# 02_AFE.net
KiCad netlist of a schematic drawn in Altium Designer
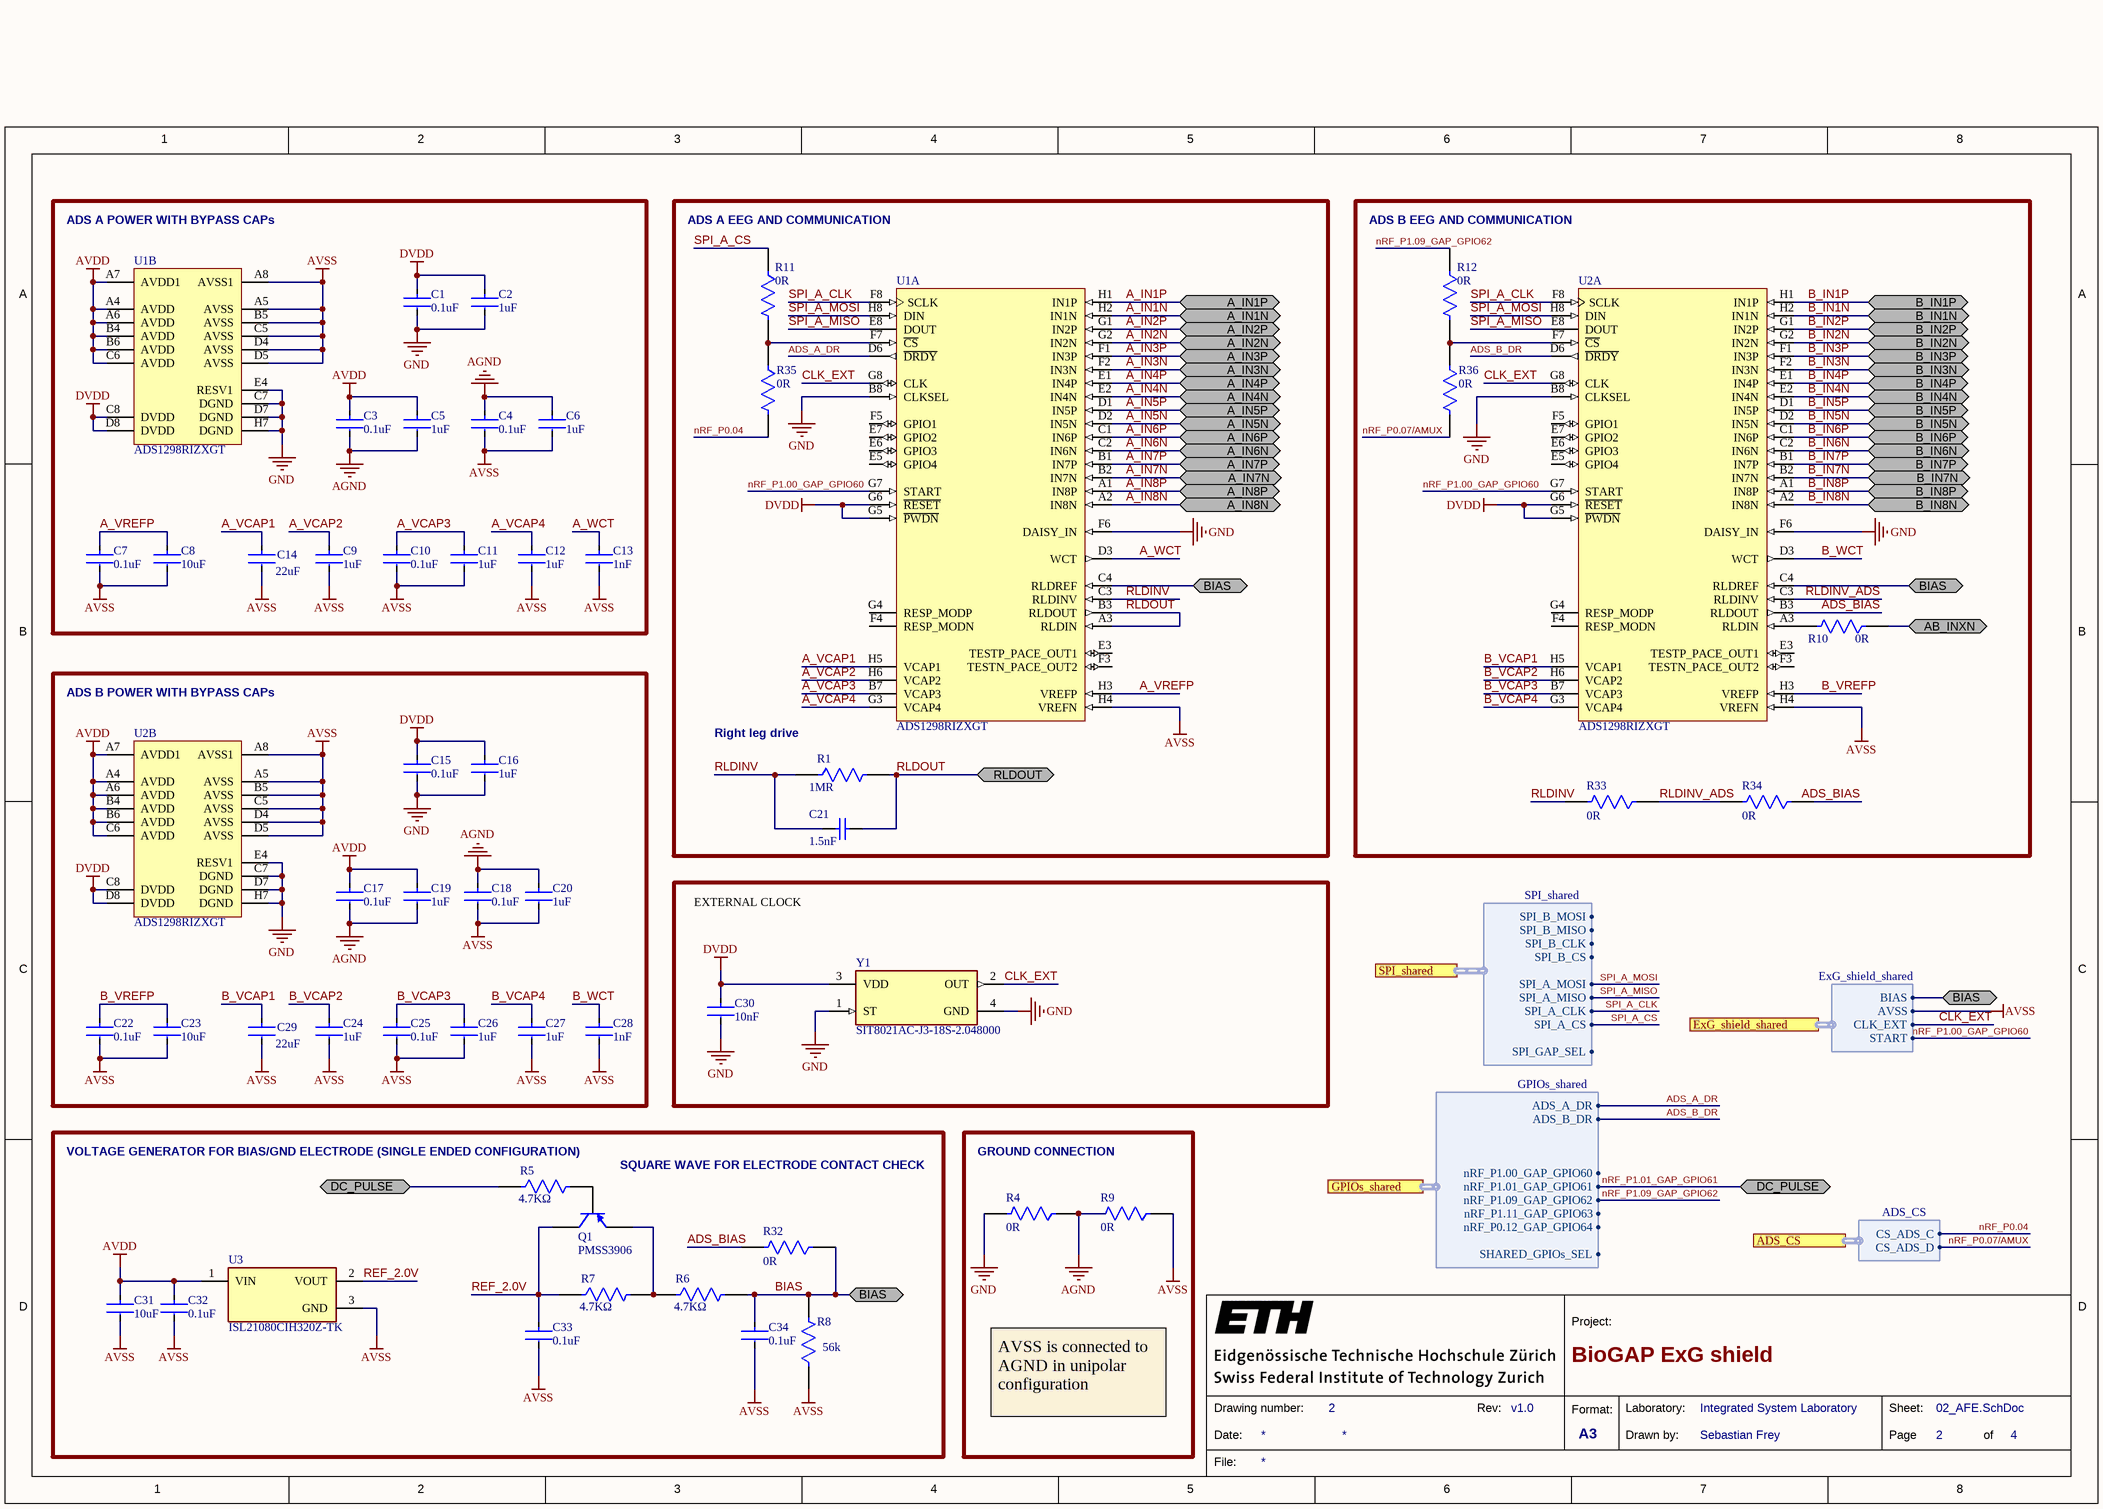
[diagram p0: 02_AFE.SchDoc]

(export (version "E")
  (design (tool "Eeschema 10.0.6"))
  (components
    (comp (ref "C1")
      (value "CL05A104KA5NNNC")
      (footprint "FP-CL278-IPC_C")
      (description "Cap Ceramic 100nF 25V X5R ±10% SMD 0402 +85°C Paper T/R")
      (fields
        (field (name "VOLTAGE") "25V")
        (field (name "TOLERANCE") "10%")
        (field (name "CAPACITANCE") "0.1uF")
      )
      (libsource (lib "Altium Content Vault") (part "b4654b650e69147ec39a6b967a45e02"))
    )
    (comp (ref "C2")
      (value "CL05A105KP5NNNC")
      (footprint "FP-CL511-IPC_C")
      (description "Cap Ceramic 1uF 10V X5R ±10% SMD 0402 +85°C Paper T/R")
      (fields (field (name "CAPACITANCE") "1uF") (field (name "TOLERANCE") "10%"))
      (libsource (lib "Altium Content Vault") (part "b4654b650e69147ec39a6b967a45e02"))
    )
    (comp (ref "C3")
      (value "CL05A104KA5NNNC")
      (footprint "FP-CL278-IPC_C")
      (description "Cap Ceramic 100nF 25V X5R ±10% SMD 0402 +85°C Paper T/R")
      (fields
        (field (name "VOLTAGE") "25V")
        (field (name "TOLERANCE") "10%")
        (field (name "CAPACITANCE") "0.1uF")
      )
      (libsource (lib "Altium Content Vault") (part "b4654b650e69147ec39a6b967a45e02"))
    )
    (comp (ref "C4")
      (value "CL05A104KA5NNNC")
      (footprint "FP-CL278-IPC_C")
      (description "Cap Ceramic 100nF 25V X5R ±10% SMD 0402 +85°C Paper T/R")
      (fields
        (field (name "VOLTAGE") "25V")
        (field (name "TOLERANCE") "10%")
        (field (name "CAPACITANCE") "0.1uF")
      )
      (libsource (lib "Altium Content Vault") (part "b4654b650e69147ec39a6b967a45e02"))
    )
    (comp (ref "C5")
      (value "CL05A105KP5NNNC")
      (footprint "FP-CL511-IPC_C")
      (description "Cap Ceramic 1uF 10V X5R ±10% SMD 0402 +85°C Paper T/R")
      (fields (field (name "CAPACITANCE") "1uF") (field (name "TOLERANCE") "10%"))
      (libsource (lib "Altium Content Vault") (part "b4654b650e69147ec39a6b967a45e02"))
    )
    (comp (ref "C6")
      (value "CL05A105KP5NNNC")
      (footprint "FP-CL511-IPC_C")
      (description "Cap Ceramic 1uF 10V X5R ±10% SMD 0402 +85°C Paper T/R")
      (fields (field (name "CAPACITANCE") "1uF") (field (name "TOLERANCE") "10%"))
      (libsource (lib "Altium Content Vault") (part "b4654b650e69147ec39a6b967a45e02"))
    )
    (comp (ref "C7")
      (value "CL05A104KA5NNNC")
      (footprint "FP-CL278-IPC_C")
      (description "Cap Ceramic 100nF 25V X5R ±10% SMD 0402 +85°C Paper T/R")
      (fields
        (field (name "VOLTAGE") "25V")
        (field (name "TOLERANCE") "10%")
        (field (name "CAPACITANCE") "0.1uF")
      )
      (libsource (lib "Altium Content Vault") (part "b4654b650e69147ec39a6b967a45e02"))
    )
    (comp (ref "C8")
      (value "CL05A106MP8NUB8")
      (footprint "FP-CL07-IPC_C")
      (description "Cap Ceramic 10uF 10V X5R ±20% SMD 0402 +85°C Paper T/R")
      (fields (field (name "CAPACITANCE") "10uF") (field (name "TOLERANCE") "20%"))
      (libsource (lib "Altium Content Vault") (part "b4654b650e69147ec39a6b967a45e02"))
    )
    (comp (ref "C9")
      (value "CL05A105KP5NNNC")
      (footprint "FP-CL511-IPC_C")
      (description "Cap Ceramic 1uF 10V X5R ±10% SMD 0402 +85°C Paper T/R")
      (fields (field (name "CAPACITANCE") "1uF") (field (name "TOLERANCE") "10%"))
      (libsource (lib "Altium Content Vault") (part "b4654b650e69147ec39a6b967a45e02"))
    )
    (comp (ref "C10")
      (value "CL05A104KA5NNNC")
      (footprint "FP-CL278-IPC_C")
      (description "Cap Ceramic 100nF 25V X5R ±10% SMD 0402 +85°C Paper T/R")
      (fields
        (field (name "VOLTAGE") "25V")
        (field (name "TOLERANCE") "10%")
        (field (name "CAPACITANCE") "0.1uF")
      )
      (libsource (lib "Altium Content Vault") (part "b4654b650e69147ec39a6b967a45e02"))
    )
    (comp (ref "C11")
      (value "CL05A105KP5NNNC")
      (footprint "FP-CL511-IPC_C")
      (description "Cap Ceramic 1uF 10V X5R ±10% SMD 0402 +85°C Paper T/R")
      (fields (field (name "CAPACITANCE") "1uF") (field (name "TOLERANCE") "10%"))
      (libsource (lib "Altium Content Vault") (part "b4654b650e69147ec39a6b967a45e02"))
    )
    (comp (ref "C12")
      (value "CL05A105KP5NNNC")
      (footprint "FP-CL511-IPC_C")
      (description "Cap Ceramic 1uF 10V X5R ±10% SMD 0402 +85°C Paper T/R")
      (fields (field (name "CAPACITANCE") "1uF") (field (name "TOLERANCE") "10%"))
      (libsource (lib "Altium Content Vault") (part "b4654b650e69147ec39a6b967a45e02"))
    )
    (comp (ref "C13")
      (value "04025C102KAT2A")
      (footprint "FP-0402-L_1_0_1-W_0_5_0_1-IPC_B")
      (description "General Purpose Ceramic Capacitor, 0402, 1nF, 10%, X7R, 15%, 50V")
      (fields
        (field (name "CAPACITANCE") "1nF")
        (field (name "TOLERANCE") "10%")
        (field (name "VOLTAGE") "50V")
      )
      (libsource (lib "Altium Content Vault") (part "b4654b650e69147ec39a6b967a45e02"))
    )
    (comp (ref "C14")
      (value "CL05A226MQ5QUNC")
      (footprint "FP-CL746-IPC_C")
      (description "Cap Ceramic 22uF 6.3V X5R ±20% SMD 0402 +85°C Paper T/R")
      (fields (field (name "TOLERANCE") "20%") (field (name "CAPACITANCE") "22uF"))
      (libsource (lib "Altium Content Vault") (part "b4654b650e69147ec39a6b967a45e02"))
    )
    (comp (ref "C15")
      (value "CL05A104KA5NNNC")
      (footprint "FP-CL278-IPC_C")
      (description "Cap Ceramic 100nF 25V X5R ±10% SMD 0402 +85°C Paper T/R")
      (fields
        (field (name "VOLTAGE") "25V")
        (field (name "TOLERANCE") "10%")
        (field (name "CAPACITANCE") "0.1uF")
      )
      (libsource (lib "Altium Content Vault") (part "b4654b650e69147ec39a6b967a45e02"))
    )
    (comp (ref "C16")
      (value "CL05A105KP5NNNC")
      (footprint "FP-CL511-IPC_C")
      (description "Cap Ceramic 1uF 10V X5R ±10% SMD 0402 +85°C Paper T/R")
      (fields (field (name "CAPACITANCE") "1uF") (field (name "TOLERANCE") "10%"))
      (libsource (lib "Altium Content Vault") (part "b4654b650e69147ec39a6b967a45e02"))
    )
    (comp (ref "C17")
      (value "CL05A104KA5NNNC")
      (footprint "FP-CL278-IPC_C")
      (description "Cap Ceramic 100nF 25V X5R ±10% SMD 0402 +85°C Paper T/R")
      (fields
        (field (name "VOLTAGE") "25V")
        (field (name "TOLERANCE") "10%")
        (field (name "CAPACITANCE") "0.1uF")
      )
      (libsource (lib "Altium Content Vault") (part "b4654b650e69147ec39a6b967a45e02"))
    )
    (comp (ref "C18")
      (value "CL05A104KA5NNNC")
      (footprint "FP-CL278-IPC_C")
      (description "Cap Ceramic 100nF 25V X5R ±10% SMD 0402 +85°C Paper T/R")
      (fields
        (field (name "VOLTAGE") "25V")
        (field (name "TOLERANCE") "10%")
        (field (name "CAPACITANCE") "0.1uF")
      )
      (libsource (lib "Altium Content Vault") (part "b4654b650e69147ec39a6b967a45e02"))
    )
    (comp (ref "C19")
      (value "CL05A105KP5NNNC")
      (footprint "FP-CL511-IPC_C")
      (description "Cap Ceramic 1uF 10V X5R ±10% SMD 0402 +85°C Paper T/R")
      (fields (field (name "CAPACITANCE") "1uF") (field (name "TOLERANCE") "10%"))
      (libsource (lib "Altium Content Vault") (part "b4654b650e69147ec39a6b967a45e02"))
    )
    (comp (ref "C20")
      (value "CL05A105KP5NNNC")
      (footprint "FP-CL511-IPC_C")
      (description "Cap Ceramic 1uF 10V X5R ±10% SMD 0402 +85°C Paper T/R")
      (fields (field (name "CAPACITANCE") "1uF") (field (name "TOLERANCE") "10%"))
      (libsource (lib "Altium Content Vault") (part "b4654b650e69147ec39a6b967a45e02"))
    )
    (comp (ref "C21")
      (value "GRM155R71H152KA01D")
      (footprint "CAPC1005X55X25NL05T10")
      (fields (field (name "MANUFACTURER") "Murata") (field (name "CAPACITANCE") "1.5nF"))
      (libsource (lib "Altium Content Vault") (part "CAP"))
    )
    (comp (ref "C22")
      (value "CL05A104KA5NNNC")
      (footprint "FP-CL278-IPC_C")
      (description "Cap Ceramic 100nF 25V X5R ±10% SMD 0402 +85°C Paper T/R")
      (fields
        (field (name "VOLTAGE") "25V")
        (field (name "TOLERANCE") "10%")
        (field (name "CAPACITANCE") "0.1uF")
      )
      (libsource (lib "Altium Content Vault") (part "b4654b650e69147ec39a6b967a45e02"))
    )
    (comp (ref "C23")
      (value "CL05A106MP8NUB8")
      (footprint "FP-CL07-IPC_C")
      (description "Cap Ceramic 10uF 10V X5R ±20% SMD 0402 +85°C Paper T/R")
      (fields (field (name "CAPACITANCE") "10uF") (field (name "TOLERANCE") "20%"))
      (libsource (lib "Altium Content Vault") (part "b4654b650e69147ec39a6b967a45e02"))
    )
    (comp (ref "C24")
      (value "CL05A105KP5NNNC")
      (footprint "FP-CL511-IPC_C")
      (description "Cap Ceramic 1uF 10V X5R ±10% SMD 0402 +85°C Paper T/R")
      (fields (field (name "CAPACITANCE") "1uF") (field (name "TOLERANCE") "10%"))
      (libsource (lib "Altium Content Vault") (part "b4654b650e69147ec39a6b967a45e02"))
    )
    (comp (ref "C25")
      (value "CL05A104KA5NNNC")
      (footprint "FP-CL278-IPC_C")
      (description "Cap Ceramic 100nF 25V X5R ±10% SMD 0402 +85°C Paper T/R")
      (fields
        (field (name "VOLTAGE") "25V")
        (field (name "TOLERANCE") "10%")
        (field (name "CAPACITANCE") "0.1uF")
      )
      (libsource (lib "Altium Content Vault") (part "b4654b650e69147ec39a6b967a45e02"))
    )
    (comp (ref "C26")
      (value "CL05A105KP5NNNC")
      (footprint "FP-CL511-IPC_C")
      (description "Cap Ceramic 1uF 10V X5R ±10% SMD 0402 +85°C Paper T/R")
      (fields (field (name "CAPACITANCE") "1uF") (field (name "TOLERANCE") "10%"))
      (libsource (lib "Altium Content Vault") (part "b4654b650e69147ec39a6b967a45e02"))
    )
    (comp (ref "C27")
      (value "CL05A105KP5NNNC")
      (footprint "FP-CL511-IPC_C")
      (description "Cap Ceramic 1uF 10V X5R ±10% SMD 0402 +85°C Paper T/R")
      (fields (field (name "CAPACITANCE") "1uF") (field (name "TOLERANCE") "10%"))
      (libsource (lib "Altium Content Vault") (part "b4654b650e69147ec39a6b967a45e02"))
    )
    (comp (ref "C28")
      (value "04025C102KAT2A")
      (footprint "FP-0402-L_1_0_1-W_0_5_0_1-IPC_B")
      (description "General Purpose Ceramic Capacitor, 0402, 1nF, 10%, X7R, 15%, 50V")
      (fields
        (field (name "CAPACITANCE") "1nF")
        (field (name "TOLERANCE") "10%")
        (field (name "VOLTAGE") "50V")
      )
      (libsource (lib "Altium Content Vault") (part "b4654b650e69147ec39a6b967a45e02"))
    )
    (comp (ref "C29")
      (value "CL05A226MQ5QUNC")
      (footprint "FP-CL746-IPC_C")
      (description "Cap Ceramic 22uF 6.3V X5R ±20% SMD 0402 +85°C Paper T/R")
      (fields (field (name "TOLERANCE") "20%") (field (name "CAPACITANCE") "22uF"))
      (libsource (lib "Altium Content Vault") (part "b4654b650e69147ec39a6b967a45e02"))
    )
    (comp (ref "C30")
      (value "CGA2B3X7R1V103K050BB")
      (footprint "FP-CGA2B-MFG")
      (description "Cap Ceramic 10nF 35V X7R 10% Pad SMD 0402 +125°C Automotive T/R")
      (fields (field (name "CAPACITANCE") "10nF") (field (name "TOLERANCE") "10%"))
      (libsource (lib "Altium Content Vault") (part "b4654b650e69147ec39a6b967a45e02"))
    )
    (comp (ref "C31")
      (value "CL05A106MP8NUB8")
      (footprint "FP-CL07-IPC_C")
      (description "Cap Ceramic 10uF 10V X5R ±20% SMD 0402 +85°C Paper T/R")
      (fields (field (name "CAPACITANCE") "10uF") (field (name "TOLERANCE") "20%"))
      (libsource (lib "Altium Content Vault") (part "b4654b650e69147ec39a6b967a45e02"))
    )
    (comp (ref "C32")
      (value "CL05A104KA5NNNC")
      (footprint "FP-CL278-IPC_C")
      (description "Cap Ceramic 100nF 25V X5R ±10% SMD 0402 +85°C Paper T/R")
      (fields
        (field (name "VOLTAGE") "25V")
        (field (name "TOLERANCE") "10%")
        (field (name "CAPACITANCE") "0.1uF")
      )
      (libsource (lib "Altium Content Vault") (part "b4654b650e69147ec39a6b967a45e02"))
    )
    (comp (ref "C33")
      (value "CL05A104KA5NNNC")
      (footprint "FP-CL278-IPC_C")
      (description "Cap Ceramic 100nF 25V X5R ±10% SMD 0402 +85°C Paper T/R")
      (fields
        (field (name "VOLTAGE") "25V")
        (field (name "TOLERANCE") "10%")
        (field (name "CAPACITANCE") "0.1uF")
      )
      (libsource (lib "Altium Content Vault") (part "b4654b650e69147ec39a6b967a45e02"))
    )
    (comp (ref "C34")
      (value "CL05A104KA5NNNC")
      (footprint "FP-CL278-IPC_C")
      (description "Cap Ceramic 100nF 25V X5R ±10% SMD 0402 +85°C Paper T/R")
      (fields
        (field (name "VOLTAGE") "25V")
        (field (name "TOLERANCE") "10%")
        (field (name "CAPACITANCE") "0.1uF")
      )
      (libsource (lib "Altium Content Vault") (part "b4654b650e69147ec39a6b967a45e02"))
    )
    (comp (ref "Q1")
      (value "PMSS3906")
      (footprint "SOT323_N")
      (description "PNP Switching Transistor")
      (fields (field (name "PUBLISHER") "Altium Limited"))
      (libsource (lib "EEG_SchLib") (part "PMSS3906"))
    )
    (comp (ref "R1")
      (value "MCS04020C1004FE000")
      (footprint "FP-MCS0402-IPC_C")
      (description "RES SMD 1M OHM 1% 1/10W 0402")
      (fields (field (name "TOLERANCE") "1%") (field (name "RESISTANCE") "1MR"))
      (libsource (lib "Altium Content Vault") (part "1029c3af85768c4190bb7ad29bc67b5"))
    )
    (comp (ref "R4")
      (value "RC0402FR-070RL")
      (footprint "FP-RC0402-0_4-IPC_A")
      (description "RES SMD 0 OHM JUMPER 1/16W 0402")
      (fields (field (name "RESISTANCE") "0R") (field (name "TOLERANCE") "1%"))
      (libsource (lib "Altium Content Vault") (part "1029c3af85768c4190bb7ad29bc67b5"))
    )
    (comp (ref "R5")
      (value "4.7KΩ")
      (footprint "FP-RT0402-MFG")
      (description "RES 4.70K OHM 1/16W 1% SMD 0402")
      (fields
        (field (name "MANUFACTURER PART NUMBER") "RT0402FRE074K7L")
        (field (name "MANUFACTURER") "Yageo")
      )
      (libsource (lib "Altium Content Vault") (part "1029c3af85768c4190bb7ad29bc67b5"))
    )
    (comp (ref "R6")
      (value "4.7KΩ")
      (footprint "FP-RT0402-MFG")
      (description "RES 4.70K OHM 1/16W 1% SMD 0402")
      (fields
        (field (name "MANUFACTURER PART NUMBER") "RT0402FRE074K7L")
        (field (name "MANUFACTURER") "Yageo")
      )
      (libsource (lib "Altium Content Vault") (part "1029c3af85768c4190bb7ad29bc67b5"))
    )
    (comp (ref "R7")
      (value "4.7KΩ")
      (footprint "FP-RT0402-MFG")
      (description "RES 4.70K OHM 1/16W 1% SMD 0402")
      (fields
        (field (name "MANUFACTURER PART NUMBER") "RT0402FRE074K7L")
        (field (name "MANUFACTURER") "Yageo")
      )
      (libsource (lib "Altium Content Vault") (part "1029c3af85768c4190bb7ad29bc67b5"))
    )
    (comp (ref "R8")
      (value "RR0510P-563-D")
      (footprint "FP-RR0510-MFG")
      (description "56kΩ ±0.5% 0.0625W 1/16W Chip Resistor 0402 (1005 Metric) Thin Film")
      (fields (field (name "TOLERANCE") "0.5%") (field (name "RESISTANCE") "56k"))
      (libsource (lib "Altium Content Vault") (part "1029c3af85768c4190bb7ad29bc67b5"))
    )
    (comp (ref "R9")
      (value "RC0402FR-070RL")
      (footprint "FP-RC0402-0_4-IPC_A")
      (description "RES SMD 0 OHM JUMPER 1/16W 0402")
      (fields (field (name "RESISTANCE") "0R") (field (name "TOLERANCE") "1%"))
      (libsource (lib "Altium Content Vault") (part "1029c3af85768c4190bb7ad29bc67b5"))
    )
    (comp (ref "R10")
      (value "RC0402FR-070RL")
      (footprint "FP-RC0402-0_4-IPC_C")
      (description "RES SMD 0 OHM JUMPER 1/16W 0402")
      (fields (field (name "RESISTANCE") "0R") (field (name "TOLERANCE") "1%"))
      (libsource (lib "Altium Content Vault") (part "1029c3af85768c4190bb7ad29bc67b5"))
    )
    (comp (ref "R11")
      (value "RC0402FR-070RL")
      (footprint "FP-RC0402-0_4-IPC_C")
      (description "RES SMD 0 OHM JUMPER 1/16W 0402")
      (fields (field (name "RESISTANCE") "0R") (field (name "TOLERANCE") "1%"))
      (libsource (lib "Altium Content Vault") (part "1029c3af85768c4190bb7ad29bc67b5"))
    )
    (comp (ref "R12")
      (value "RC0402FR-070RL")
      (footprint "FP-RC0402-0_4-IPC_C")
      (description "RES SMD 0 OHM JUMPER 1/16W 0402")
      (fields (field (name "RESISTANCE") "0R") (field (name "TOLERANCE") "1%"))
      (libsource (lib "Altium Content Vault") (part "1029c3af85768c4190bb7ad29bc67b5"))
    )
    (comp (ref "R32")
      (value "RC0402FR-070RL")
      (footprint "FP-RC0402-0_4-IPC_C")
      (description "RES SMD 0 OHM JUMPER 1/16W 0402")
      (fields (field (name "RESISTANCE") "0R") (field (name "TOLERANCE") "1%"))
      (libsource (lib "Altium Content Vault") (part "1029c3af85768c4190bb7ad29bc67b5"))
    )
    (comp (ref "R33")
      (value "RC0402FR-070RL")
      (footprint "FP-RC0402-0_4-IPC_C")
      (description "RES SMD 0 OHM JUMPER 1/16W 0402")
      (fields (field (name "RESISTANCE") "0R") (field (name "TOLERANCE") "1%"))
      (libsource (lib "Altium Content Vault") (part "1029c3af85768c4190bb7ad29bc67b5"))
    )
    (comp (ref "R34")
      (value "RC0402FR-070RL")
      (footprint "FP-RC0402-0_4-IPC_C")
      (description "RES SMD 0 OHM JUMPER 1/16W 0402")
      (fields (field (name "RESISTANCE") "0R") (field (name "TOLERANCE") "1%"))
      (libsource (lib "Altium Content Vault") (part "1029c3af85768c4190bb7ad29bc67b5"))
    )
    (comp (ref "R35")
      (value "RC0402FR-070RL")
      (footprint "FP-RC0402-0_4-IPC_C")
      (description "RES SMD 0 OHM JUMPER 1/16W 0402")
      (fields (field (name "RESISTANCE") "0R") (field (name "TOLERANCE") "1%"))
      (libsource (lib "Altium Content Vault") (part "1029c3af85768c4190bb7ad29bc67b5"))
    )
    (comp (ref "R36")
      (value "RC0402FR-070RL")
      (footprint "FP-RC0402-0_4-IPC_C")
      (description "RES SMD 0 OHM JUMPER 1/16W 0402")
      (fields (field (name "RESISTANCE") "0R") (field (name "TOLERANCE") "1%"))
      (libsource (lib "Altium Content Vault") (part "1029c3af85768c4190bb7ad29bc67b5"))
    )
    (comp (ref "U1")
      (value "ADS1298RIZXGT")
      (footprint "TI-ZXG64")
      (fields (field (name "MANUFACTURER") "Texas Instruments"))
      (libsource (lib "Altium Content Vault") (part "TI-ADS1298RZXG64"))
    )
    (comp (ref "U2")
      (value "ADS1298RIZXGT")
      (footprint "TI-ZXG64")
      (fields (field (name "MANUFACTURER") "Texas Instruments"))
      (libsource (lib "Altium Content Vault") (part "TI-ADS1298RZXG64"))
    )
    (comp (ref "U3")
      (value "ISL21080CIH320Z-TK")
      (footprint "FP-P3_064A-IPC_C")
      (description "IC VREF SERIES 0.3% SOT23-3")
      (fields (field (name "TOLERANCE") "0.3%"))
      (libsource (lib "Altium Content Vault") (part "d4f0b6a9f4a6a4d0e4630da6419d1e9"))
    )
    (comp (ref "Y1")
      (value "SIT8021AC-J3-18S-2.048000")
      (footprint "FP-SiT8021-MFG")
      (description "MEMS OSC 2.048MHZ LVCMOS")
      (libsource (lib "Altium Content Vault") (part "1ca1ac4b74c81e26385f243382fd306"))
    )
  )
  (nets
    (net (code "5") (name "/AB_INXN") (class "Default")
      (node (ref "R10") (pin "1") (pinfunction "1_1") (pintype "passive"))
    )
    (net (code "6") (name "/ADS_A_DR") (class "Default")
      (node (ref "U1") (pin "D6") (pinfunction "~{DRDY}_D6") (pintype "output"))
    )
    (net (code "7") (name "/ADS_BIAS") (class "Default")
      (node (ref "R32") (pin "2") (pinfunction "2_2") (pintype "passive"))
      (node (ref "R34") (pin "1") (pinfunction "1_1") (pintype "passive"))
      (node (ref "U2") (pin "B3") (pinfunction "RLDOUT_B3") (pintype "output"))
    )
    (net (code "8") (name "/ADS_B_DR") (class "Default")
      (node (ref "U2") (pin "D6") (pinfunction "~{DRDY}_D6") (pintype "output"))
    )
    (net (code "9") (name "/A_IN1N") (class "Default")
      (node (ref "U1") (pin "H2") (pinfunction "IN1N_H2") (pintype "input"))
    )
    (net (code "10") (name "/A_IN1P") (class "Default")
      (node (ref "U1") (pin "H1") (pinfunction "IN1P_H1") (pintype "input"))
    )
    (net (code "11") (name "/A_IN2N") (class "Default")
      (node (ref "U1") (pin "G2") (pinfunction "IN2N_G2") (pintype "input"))
    )
    (net (code "12") (name "/A_IN2P") (class "Default")
      (node (ref "U1") (pin "G1") (pinfunction "IN2P_G1") (pintype "input"))
    )
    (net (code "13") (name "/A_IN3N") (class "Default")
      (node (ref "U1") (pin "F2") (pinfunction "IN3N_F2") (pintype "input"))
    )
    (net (code "14") (name "/A_IN3P") (class "Default")
      (node (ref "U1") (pin "F1") (pinfunction "IN3P_F1") (pintype "input"))
    )
    (net (code "15") (name "/A_IN4N") (class "Default")
      (node (ref "U1") (pin "E2") (pinfunction "IN4N_E2") (pintype "input"))
    )
    (net (code "16") (name "/A_IN4P") (class "Default")
      (node (ref "U1") (pin "E1") (pinfunction "IN4P_E1") (pintype "input"))
    )
    (net (code "17") (name "/A_IN5N") (class "Default")
      (node (ref "U1") (pin "D2") (pinfunction "IN5N_D2") (pintype "input"))
    )
    (net (code "18") (name "/A_IN5P") (class "Default")
      (node (ref "U1") (pin "D1") (pinfunction "IN5P_D1") (pintype "input"))
    )
    (net (code "19") (name "/A_IN6N") (class "Default")
      (node (ref "U1") (pin "C2") (pinfunction "IN6N_C2") (pintype "input"))
    )
    (net (code "20") (name "/A_IN6P") (class "Default")
      (node (ref "U1") (pin "C1") (pinfunction "IN6P_C1") (pintype "input"))
    )
    (net (code "21") (name "/A_IN7N") (class "Default")
      (node (ref "U1") (pin "B2") (pinfunction "IN7N_B2") (pintype "input"))
    )
    (net (code "22") (name "/A_IN7P") (class "Default")
      (node (ref "U1") (pin "B1") (pinfunction "IN7P_B1") (pintype "input"))
    )
    (net (code "23") (name "/A_IN8N") (class "Default")
      (node (ref "U1") (pin "A2") (pinfunction "IN8N_A2") (pintype "input"))
    )
    (net (code "24") (name "/A_IN8P") (class "Default")
      (node (ref "U1") (pin "A1") (pinfunction "IN8P_A1") (pintype "input"))
    )
    (net (code "25") (name "/A_VCAP1") (class "Default")
      (node (ref "C14") (pin "1") (pinfunction "1_1") (pintype "passive"))
      (node (ref "U1") (pin "H5") (pinfunction "VCAP1_H5") (pintype "passive"))
    )
    (net (code "26") (name "/A_VCAP2") (class "Default")
      (node (ref "C9") (pin "1") (pinfunction "1_1") (pintype "passive"))
      (node (ref "U1") (pin "H6") (pinfunction "VCAP2_H6") (pintype "passive"))
    )
    (net (code "27") (name "/A_VCAP3") (class "Default")
      (node (ref "C10") (pin "1") (pinfunction "1_1") (pintype "passive"))
      (node (ref "C11") (pin "1") (pinfunction "1_1") (pintype "passive"))
      (node (ref "U1") (pin "B7") (pinfunction "VCAP3_B7") (pintype "passive"))
    )
    (net (code "28") (name "/A_VCAP4") (class "Default")
      (node (ref "C12") (pin "1") (pinfunction "1_1") (pintype "passive"))
      (node (ref "U1") (pin "G3") (pinfunction "VCAP4_G3") (pintype "passive"))
    )
    (net (code "29") (name "/A_VREFP") (class "Default")
      (node (ref "C7") (pin "1") (pinfunction "1_1") (pintype "passive"))
      (node (ref "C8") (pin "1") (pinfunction "1_1") (pintype "passive"))
      (node (ref "U1") (pin "H3") (pinfunction "VREFP_H3") (pintype "input"))
    )
    (net (code "30") (name "/A_WCT") (class "Default")
      (node (ref "C13") (pin "1") (pinfunction "1_1") (pintype "passive"))
      (node (ref "U1") (pin "D3") (pinfunction "WCT_D3") (pintype "output"))
    )
    (net (code "31") (name "/BIAS") (class "Default")
      (node (ref "C34") (pin "1") (pinfunction "1_1") (pintype "passive"))
      (node (ref "R32") (pin "1") (pinfunction "1_1") (pintype "passive"))
      (node (ref "R6") (pin "2") (pinfunction "2_2") (pintype "passive"))
      (node (ref "R8") (pin "2") (pinfunction "2_2") (pintype "passive"))
      (node (ref "U1") (pin "C4") (pinfunction "RLDREF_C4") (pintype "input"))
      (node (ref "U2") (pin "C4") (pinfunction "RLDREF_C4") (pintype "input"))
    )
    (net (code "32") (name "/B_IN1N") (class "Default")
      (node (ref "U2") (pin "H2") (pinfunction "IN1N_H2") (pintype "input"))
    )
    (net (code "33") (name "/B_IN1P") (class "Default")
      (node (ref "U2") (pin "H1") (pinfunction "IN1P_H1") (pintype "input"))
    )
    (net (code "34") (name "/B_IN2N") (class "Default")
      (node (ref "U2") (pin "G2") (pinfunction "IN2N_G2") (pintype "input"))
    )
    (net (code "35") (name "/B_IN2P") (class "Default")
      (node (ref "U2") (pin "G1") (pinfunction "IN2P_G1") (pintype "input"))
    )
    (net (code "36") (name "/B_IN3N") (class "Default")
      (node (ref "U2") (pin "F2") (pinfunction "IN3N_F2") (pintype "input"))
    )
    (net (code "37") (name "/B_IN3P") (class "Default")
      (node (ref "U2") (pin "F1") (pinfunction "IN3P_F1") (pintype "input"))
    )
    (net (code "38") (name "/B_IN4N") (class "Default")
      (node (ref "U2") (pin "E2") (pinfunction "IN4N_E2") (pintype "input"))
    )
    (net (code "39") (name "/B_IN4P") (class "Default")
      (node (ref "U2") (pin "E1") (pinfunction "IN4P_E1") (pintype "input"))
    )
    (net (code "40") (name "/B_IN5N") (class "Default")
      (node (ref "U2") (pin "D2") (pinfunction "IN5N_D2") (pintype "input"))
    )
    (net (code "41") (name "/B_IN5P") (class "Default")
      (node (ref "U2") (pin "D1") (pinfunction "IN5P_D1") (pintype "input"))
    )
    (net (code "42") (name "/B_IN6N") (class "Default")
      (node (ref "U2") (pin "C2") (pinfunction "IN6N_C2") (pintype "input"))
    )
    (net (code "43") (name "/B_IN6P") (class "Default")
      (node (ref "U2") (pin "C1") (pinfunction "IN6P_C1") (pintype "input"))
    )
    (net (code "44") (name "/B_IN7N") (class "Default")
      (node (ref "U2") (pin "B2") (pinfunction "IN7N_B2") (pintype "input"))
    )
    (net (code "45") (name "/B_IN7P") (class "Default")
      (node (ref "U2") (pin "B1") (pinfunction "IN7P_B1") (pintype "input"))
    )
    (net (code "46") (name "/B_IN8N") (class "Default")
      (node (ref "U2") (pin "A2") (pinfunction "IN8N_A2") (pintype "input"))
    )
    (net (code "47") (name "/B_IN8P") (class "Default")
      (node (ref "U2") (pin "A1") (pinfunction "IN8P_A1") (pintype "input"))
    )
    (net (code "48") (name "/B_VCAP1") (class "Default")
      (node (ref "C29") (pin "1") (pinfunction "1_1") (pintype "passive"))
      (node (ref "U2") (pin "H5") (pinfunction "VCAP1_H5") (pintype "passive"))
    )
    (net (code "49") (name "/B_VCAP2") (class "Default")
      (node (ref "C24") (pin "1") (pinfunction "1_1") (pintype "passive"))
      (node (ref "U2") (pin "H6") (pinfunction "VCAP2_H6") (pintype "passive"))
    )
    (net (code "50") (name "/B_VCAP3") (class "Default")
      (node (ref "C25") (pin "1") (pinfunction "1_1") (pintype "passive"))
      (node (ref "C26") (pin "1") (pinfunction "1_1") (pintype "passive"))
      (node (ref "U2") (pin "B7") (pinfunction "VCAP3_B7") (pintype "passive"))
    )
    (net (code "51") (name "/B_VCAP4") (class "Default")
      (node (ref "C27") (pin "1") (pinfunction "1_1") (pintype "passive"))
      (node (ref "U2") (pin "G3") (pinfunction "VCAP4_G3") (pintype "passive"))
    )
    (net (code "52") (name "/B_VREFP") (class "Default")
      (node (ref "C22") (pin "1") (pinfunction "1_1") (pintype "passive"))
      (node (ref "C23") (pin "1") (pinfunction "1_1") (pintype "passive"))
      (node (ref "U2") (pin "H3") (pinfunction "VREFP_H3") (pintype "input"))
    )
    (net (code "53") (name "/B_WCT") (class "Default")
      (node (ref "C28") (pin "1") (pinfunction "1_1") (pintype "passive"))
      (node (ref "U2") (pin "D3") (pinfunction "WCT_D3") (pintype "output"))
    )
    (net (code "54") (name "/CLK_EXT") (class "Default")
      (node (ref "U1") (pin "G8") (pinfunction "CLK_G8") (pintype "bidirectional"))
      (node (ref "U2") (pin "G8") (pinfunction "CLK_G8") (pintype "bidirectional"))
      (node (ref "Y1") (pin "2") (pinfunction "OUT_2") (pintype "output"))
    )
    (net (code "55") (name "/REF_2.0V") (class "Default")
      (node (ref "C33") (pin "1") (pinfunction "1_1") (pintype "passive"))
      (node (ref "Q1") (pin "3") (pinfunction "C_3") (pintype "passive"))
      (node (ref "R7") (pin "1") (pinfunction "1_1") (pintype "passive"))
      (node (ref "U3") (pin "2") (pinfunction "VOUT_2") (pintype "power_in"))
    )
    (net (code "56") (name "/RLDINV") (class "Default")
      (node (ref "C21") (pin "1") (pinfunction "1_1") (pintype "passive"))
      (node (ref "R1") (pin "1") (pinfunction "1_1") (pintype "passive"))
      (node (ref "R33") (pin "2") (pinfunction "2_2") (pintype "passive"))
      (node (ref "U1") (pin "C3") (pinfunction "RLDINV_C3") (pintype "input"))
    )
    (net (code "57") (name "/RLDINV_ADS") (class "Default")
      (node (ref "R33") (pin "1") (pinfunction "1_1") (pintype "passive"))
      (node (ref "R34") (pin "2") (pinfunction "2_2") (pintype "passive"))
      (node (ref "U2") (pin "C3") (pinfunction "RLDINV_C3") (pintype "input"))
    )
    (net (code "58") (name "/RLDOUT") (class "Default")
      (node (ref "C21") (pin "2") (pinfunction "2_2") (pintype "passive"))
      (node (ref "R1") (pin "2") (pinfunction "2_2") (pintype "passive"))
      (node (ref "U1") (pin "A3") (pinfunction "RLDIN_A3") (pintype "input"))
      (node (ref "U1") (pin "B3") (pinfunction "RLDOUT_B3") (pintype "output"))
    )
    (net (code "59") (name "/SPI_A_CLK") (class "Default")
      (node (ref "U1") (pin "F8") (pinfunction "SCLK_F8") (pintype "input"))
      (node (ref "U2") (pin "F8") (pinfunction "SCLK_F8") (pintype "input"))
    )
    (net (code "60") (name "/SPI_A_CS") (class "Default")
      (node (ref "R11") (pin "1") (pinfunction "1_1") (pintype "passive"))
    )
    (net (code "61") (name "/SPI_A_MISO") (class "Default")
      (node (ref "U1") (pin "E8") (pinfunction "DOUT_E8") (pintype "tri_state"))
      (node (ref "U2") (pin "E8") (pinfunction "DOUT_E8") (pintype "tri_state"))
    )
    (net (code "62") (name "/SPI_A_MOSI") (class "Default")
      (node (ref "U1") (pin "H8") (pinfunction "DIN_H8") (pintype "input"))
      (node (ref "U2") (pin "H8") (pinfunction "DIN_H8") (pintype "input"))
    )
    (net (code "63") (name "/nRF_P0.04") (class "Default")
      (node (ref "R35") (pin "2") (pinfunction "2_2") (pintype "passive"))
    )
    (net (code "64") (name "/nRF_P0.07{slash}AMUX") (class "Default")
      (node (ref "R36") (pin "2") (pinfunction "2_2") (pintype "passive"))
    )
    (net (code "65") (name "/nRF_P1.00_GAP_GPIO60") (class "Default")
      (node (ref "U1") (pin "G7") (pinfunction "START_G7") (pintype "input"))
      (node (ref "U2") (pin "G7") (pinfunction "START_G7") (pintype "input"))
    )
    (net (code "66") (name "/nRF_P1.01_GAP_GPIO61") (class "Default")
      (node (ref "R5") (pin "1") (pinfunction "1_1") (pintype "passive"))
    )
    (net (code "67") (name "/nRF_P1.09_GAP_GPIO62") (class "Default")
      (node (ref "R12") (pin "1") (pinfunction "1_1") (pintype "passive"))
    )
    (net (code "72") (name "AGND") (class "Default")
      (node (ref "C17") (pin "2") (pinfunction "2_2") (pintype "passive"))
      (node (ref "C18") (pin "1") (pinfunction "1_1") (pintype "passive"))
      (node (ref "C19") (pin "2") (pinfunction "2_2") (pintype "passive"))
      (node (ref "C20") (pin "1") (pinfunction "1_1") (pintype "passive"))
      (node (ref "C3") (pin "2") (pinfunction "2_2") (pintype "passive"))
      (node (ref "C4") (pin "1") (pinfunction "1_1") (pintype "passive"))
      (node (ref "C5") (pin "2") (pinfunction "2_2") (pintype "passive"))
      (node (ref "C6") (pin "1") (pinfunction "1_1") (pintype "passive"))
      (node (ref "R4") (pin "1") (pinfunction "1_1") (pintype "passive"))
      (node (ref "R9") (pin "2") (pinfunction "2_2") (pintype "passive"))
    )
    (net (code "73") (name "AVDD") (class "Default")
      (node (ref "C17") (pin "1") (pinfunction "1_1") (pintype "passive"))
      (node (ref "C19") (pin "1") (pinfunction "1_1") (pintype "passive"))
      (node (ref "C3") (pin "1") (pinfunction "1_1") (pintype "passive"))
      (node (ref "C31") (pin "1") (pinfunction "1_1") (pintype "passive"))
      (node (ref "C32") (pin "1") (pinfunction "1_1") (pintype "passive"))
      (node (ref "C5") (pin "1") (pinfunction "1_1") (pintype "passive"))
      (node (ref "U1") (pin "A4") (pinfunction "AVDD_A4") (pintype "power_in"))
      (node (ref "U1") (pin "A6") (pinfunction "AVDD_A6") (pintype "power_in"))
      (node (ref "U1") (pin "A7") (pinfunction "AVDD1_A7") (pintype "power_in"))
      (node (ref "U1") (pin "B4") (pinfunction "AVDD_B4") (pintype "power_in"))
      (node (ref "U1") (pin "B6") (pinfunction "AVDD_B6") (pintype "power_in"))
      (node (ref "U1") (pin "C6") (pinfunction "AVDD_C6") (pintype "power_in"))
      (node (ref "U2") (pin "A4") (pinfunction "AVDD_A4") (pintype "power_in"))
      (node (ref "U2") (pin "A6") (pinfunction "AVDD_A6") (pintype "power_in"))
      (node (ref "U2") (pin "A7") (pinfunction "AVDD1_A7") (pintype "power_in"))
      (node (ref "U2") (pin "B4") (pinfunction "AVDD_B4") (pintype "power_in"))
      (node (ref "U2") (pin "B6") (pinfunction "AVDD_B6") (pintype "power_in"))
      (node (ref "U2") (pin "C6") (pinfunction "AVDD_C6") (pintype "power_in"))
      (node (ref "U3") (pin "1") (pinfunction "VIN_1") (pintype "power_in"))
    )
    (net (code "74") (name "AVSS") (class "Default")
      (node (ref "C10") (pin "2") (pinfunction "2_2") (pintype "passive"))
      (node (ref "C11") (pin "2") (pinfunction "2_2") (pintype "passive"))
      (node (ref "C12") (pin "2") (pinfunction "2_2") (pintype "passive"))
      (node (ref "C13") (pin "2") (pinfunction "2_2") (pintype "passive"))
      (node (ref "C14") (pin "2") (pinfunction "2_2") (pintype "passive"))
      (node (ref "C18") (pin "2") (pinfunction "2_2") (pintype "passive"))
      (node (ref "C20") (pin "2") (pinfunction "2_2") (pintype "passive"))
      (node (ref "C22") (pin "2") (pinfunction "2_2") (pintype "passive"))
      (node (ref "C23") (pin "2") (pinfunction "2_2") (pintype "passive"))
      (node (ref "C24") (pin "2") (pinfunction "2_2") (pintype "passive"))
      (node (ref "C25") (pin "2") (pinfunction "2_2") (pintype "passive"))
      (node (ref "C26") (pin "2") (pinfunction "2_2") (pintype "passive"))
      (node (ref "C27") (pin "2") (pinfunction "2_2") (pintype "passive"))
      (node (ref "C28") (pin "2") (pinfunction "2_2") (pintype "passive"))
      (node (ref "C29") (pin "2") (pinfunction "2_2") (pintype "passive"))
      (node (ref "C31") (pin "2") (pinfunction "2_2") (pintype "passive"))
      (node (ref "C32") (pin "2") (pinfunction "2_2") (pintype "passive"))
      (node (ref "C33") (pin "2") (pinfunction "2_2") (pintype "passive"))
      (node (ref "C34") (pin "2") (pinfunction "2_2") (pintype "passive"))
      (node (ref "C4") (pin "2") (pinfunction "2_2") (pintype "passive"))
      (node (ref "C6") (pin "2") (pinfunction "2_2") (pintype "passive"))
      (node (ref "C7") (pin "2") (pinfunction "2_2") (pintype "passive"))
      (node (ref "C8") (pin "2") (pinfunction "2_2") (pintype "passive"))
      (node (ref "C9") (pin "2") (pinfunction "2_2") (pintype "passive"))
      (node (ref "R8") (pin "1") (pinfunction "1_1") (pintype "passive"))
      (node (ref "R9") (pin "1") (pinfunction "1_1") (pintype "passive"))
      (node (ref "U1") (pin "A5") (pinfunction "AVSS_A5") (pintype "power_in"))
      (node (ref "U1") (pin "A8") (pinfunction "AVSS1_A8") (pintype "power_in"))
      (node (ref "U1") (pin "B5") (pinfunction "AVSS_B5") (pintype "power_in"))
      (node (ref "U1") (pin "C5") (pinfunction "AVSS_C5") (pintype "power_in"))
      (node (ref "U1") (pin "D4") (pinfunction "AVSS_D4") (pintype "power_in"))
      (node (ref "U1") (pin "D5") (pinfunction "AVSS_D5") (pintype "power_in"))
      (node (ref "U1") (pin "H4") (pinfunction "VREFN_H4") (pintype "input"))
      (node (ref "U2") (pin "A5") (pinfunction "AVSS_A5") (pintype "power_in"))
      (node (ref "U2") (pin "A8") (pinfunction "AVSS1_A8") (pintype "power_in"))
      (node (ref "U2") (pin "B5") (pinfunction "AVSS_B5") (pintype "power_in"))
      (node (ref "U2") (pin "C5") (pinfunction "AVSS_C5") (pintype "power_in"))
      (node (ref "U2") (pin "D4") (pinfunction "AVSS_D4") (pintype "power_in"))
      (node (ref "U2") (pin "D5") (pinfunction "AVSS_D5") (pintype "power_in"))
      (node (ref "U2") (pin "H4") (pinfunction "VREFN_H4") (pintype "input"))
      (node (ref "U3") (pin "3") (pinfunction "GND_3") (pintype "power_in"))
    )
    (net (code "75") (name "DVDD") (class "Default")
      (node (ref "C1") (pin "1") (pinfunction "1_1") (pintype "passive"))
      (node (ref "C15") (pin "1") (pinfunction "1_1") (pintype "passive"))
      (node (ref "C16") (pin "1") (pinfunction "1_1") (pintype "passive"))
      (node (ref "C2") (pin "1") (pinfunction "1_1") (pintype "passive"))
      (node (ref "C30") (pin "1") (pinfunction "1_1") (pintype "passive"))
      (node (ref "U1") (pin "C8") (pinfunction "DVDD_C8") (pintype "power_in"))
      (node (ref "U1") (pin "D8") (pinfunction "DVDD_D8") (pintype "power_in"))
      (node (ref "U1") (pin "G5") (pinfunction "~{PWDN}_G5") (pintype "input"))
      (node (ref "U1") (pin "G6") (pinfunction "~{RESET}_G6") (pintype "input"))
      (node (ref "U2") (pin "C8") (pinfunction "DVDD_C8") (pintype "power_in"))
      (node (ref "U2") (pin "D8") (pinfunction "DVDD_D8") (pintype "power_in"))
      (node (ref "U2") (pin "G5") (pinfunction "~{PWDN}_G5") (pintype "input"))
      (node (ref "U2") (pin "G6") (pinfunction "~{RESET}_G6") (pintype "input"))
      (node (ref "Y1") (pin "3") (pinfunction "VDD_3") (pintype "power_in"))
    )
    (net (code "76") (name "GND") (class "Default")
      (node (ref "C1") (pin "2") (pinfunction "2_2") (pintype "passive"))
      (node (ref "C15") (pin "2") (pinfunction "2_2") (pintype "passive"))
      (node (ref "C16") (pin "2") (pinfunction "2_2") (pintype "passive"))
      (node (ref "C2") (pin "2") (pinfunction "2_2") (pintype "passive"))
      (node (ref "C30") (pin "2") (pinfunction "2_2") (pintype "passive"))
      (node (ref "R4") (pin "2") (pinfunction "2_2") (pintype "passive"))
      (node (ref "U1") (pin "B8") (pinfunction "CLKSEL_B8") (pintype "input"))
      (node (ref "U1") (pin "C7") (pinfunction "DGND_C7") (pintype "power_in"))
      (node (ref "U1") (pin "D7") (pinfunction "DGND_D7") (pintype "power_in"))
      (node (ref "U1") (pin "E4") (pinfunction "RESV1_E4") (pintype "power_in"))
      (node (ref "U1") (pin "F6") (pinfunction "DAISY_IN_F6") (pintype "input"))
      (node (ref "U1") (pin "H7") (pinfunction "DGND_H7") (pintype "power_in"))
      (node (ref "U2") (pin "B8") (pinfunction "CLKSEL_B8") (pintype "input"))
      (node (ref "U2") (pin "C7") (pinfunction "DGND_C7") (pintype "power_in"))
      (node (ref "U2") (pin "D7") (pinfunction "DGND_D7") (pintype "power_in"))
      (node (ref "U2") (pin "E4") (pinfunction "RESV1_E4") (pintype "power_in"))
      (node (ref "U2") (pin "F6") (pinfunction "DAISY_IN_F6") (pintype "input"))
      (node (ref "U2") (pin "H7") (pinfunction "DGND_H7") (pintype "power_in"))
      (node (ref "Y1") (pin "1") (pinfunction "ST_1") (pintype "input"))
      (node (ref "Y1") (pin "4") (pinfunction "GND_4") (pintype "power_in"))
    )
    (net (code "77") (name "Net-(Q1-B)") (class "Default")
      (node (ref "Q1") (pin "1") (pinfunction "B_1") (pintype "passive"))
      (node (ref "R5") (pin "2") (pinfunction "2_2") (pintype "passive"))
    )
    (net (code "78") (name "Net-(Q1-E)") (class "Default")
      (node (ref "Q1") (pin "2") (pinfunction "E_2") (pintype "passive"))
      (node (ref "R6") (pin "1") (pinfunction "1_1") (pintype "passive"))
      (node (ref "R7") (pin "2") (pinfunction "2_2") (pintype "passive"))
    )
    (net (code "79") (name "Net-(U1A-~{CS})") (class "Default")
      (node (ref "R11") (pin "2") (pinfunction "2_2") (pintype "passive"))
      (node (ref "R35") (pin "1") (pinfunction "1_1") (pintype "passive"))
      (node (ref "U1") (pin "F7") (pinfunction "~{CS}_F7") (pintype "input"))
    )
    (net (code "80") (name "Net-(U2A-RLDIN)") (class "Default")
      (node (ref "R10") (pin "2") (pinfunction "2_2") (pintype "passive"))
      (node (ref "U2") (pin "A3") (pinfunction "RLDIN_A3") (pintype "input"))
    )
    (net (code "81") (name "Net-(U2A-~{CS})") (class "Default")
      (node (ref "R12") (pin "2") (pinfunction "2_2") (pintype "passive"))
      (node (ref "R36") (pin "1") (pinfunction "1_1") (pintype "passive"))
      (node (ref "U2") (pin "F7") (pinfunction "~{CS}_F7") (pintype "input"))
    )
    (net (code "82") (name "unconnected-(U1A-GPIO1-PadF5)") (class "Default")
      (node (ref "U1") (pin "F5") (pinfunction "GPIO1_F5") (pintype "bidirectional"))
    )
    (net (code "83") (name "unconnected-(U1A-GPIO2-PadE7)") (class "Default")
      (node (ref "U1") (pin "E7") (pinfunction "GPIO2_E7") (pintype "bidirectional"))
    )
    (net (code "84") (name "unconnected-(U1A-GPIO3-PadE6)") (class "Default")
      (node (ref "U1") (pin "E6") (pinfunction "GPIO3_E6") (pintype "bidirectional"))
    )
    (net (code "85") (name "unconnected-(U1A-GPIO4-PadE5)") (class "Default")
      (node (ref "U1") (pin "E5") (pinfunction "GPIO4_E5") (pintype "bidirectional"))
    )
    (net (code "86") (name "unconnected-(U1A-RESP_MODN-PadF4)") (class "Default")
      (node (ref "U1") (pin "F4") (pinfunction "RESP_MODN_F4") (pintype "passive"))
    )
    (net (code "87") (name "unconnected-(U1A-RESP_MODP-PadG4)") (class "Default")
      (node (ref "U1") (pin "G4") (pinfunction "RESP_MODP_G4") (pintype "passive"))
    )
    (net (code "88") (name "unconnected-(U1A-TESTN_PACE_OUT2-PadF3)") (class "Default")
      (node (ref "U1") (pin "F3") (pinfunction "TESTN_PACE_OUT2_F3") (pintype "bidirectional"))
    )
    (net (code "89") (name "unconnected-(U1A-TESTP_PACE_OUT1-PadE3)") (class "Default")
      (node (ref "U1") (pin "E3") (pinfunction "TESTP_PACE_OUT1_E3") (pintype "bidirectional"))
    )
    (net (code "90") (name "unconnected-(U2A-GPIO1-PadF5)") (class "Default")
      (node (ref "U2") (pin "F5") (pinfunction "GPIO1_F5") (pintype "bidirectional"))
    )
    (net (code "91") (name "unconnected-(U2A-GPIO2-PadE7)") (class "Default")
      (node (ref "U2") (pin "E7") (pinfunction "GPIO2_E7") (pintype "bidirectional"))
    )
    (net (code "92") (name "unconnected-(U2A-GPIO3-PadE6)") (class "Default")
      (node (ref "U2") (pin "E6") (pinfunction "GPIO3_E6") (pintype "bidirectional"))
    )
    (net (code "93") (name "unconnected-(U2A-GPIO4-PadE5)") (class "Default")
      (node (ref "U2") (pin "E5") (pinfunction "GPIO4_E5") (pintype "bidirectional"))
    )
    (net (code "94") (name "unconnected-(U2A-RESP_MODN-PadF4)") (class "Default")
      (node (ref "U2") (pin "F4") (pinfunction "RESP_MODN_F4") (pintype "passive"))
    )
    (net (code "95") (name "unconnected-(U2A-RESP_MODP-PadG4)") (class "Default")
      (node (ref "U2") (pin "G4") (pinfunction "RESP_MODP_G4") (pintype "passive"))
    )
    (net (code "96") (name "unconnected-(U2A-TESTN_PACE_OUT2-PadF3)") (class "Default")
      (node (ref "U2") (pin "F3") (pinfunction "TESTN_PACE_OUT2_F3") (pintype "bidirectional"))
    )
    (net (code "97") (name "unconnected-(U2A-TESTP_PACE_OUT1-PadE3)") (class "Default")
      (node (ref "U2") (pin "E3") (pinfunction "TESTP_PACE_OUT1_E3") (pintype "bidirectional"))
    )
  )
)
